# USB_to_Serial.net
KiCad netlist of a schematic drawn in Altium Designer
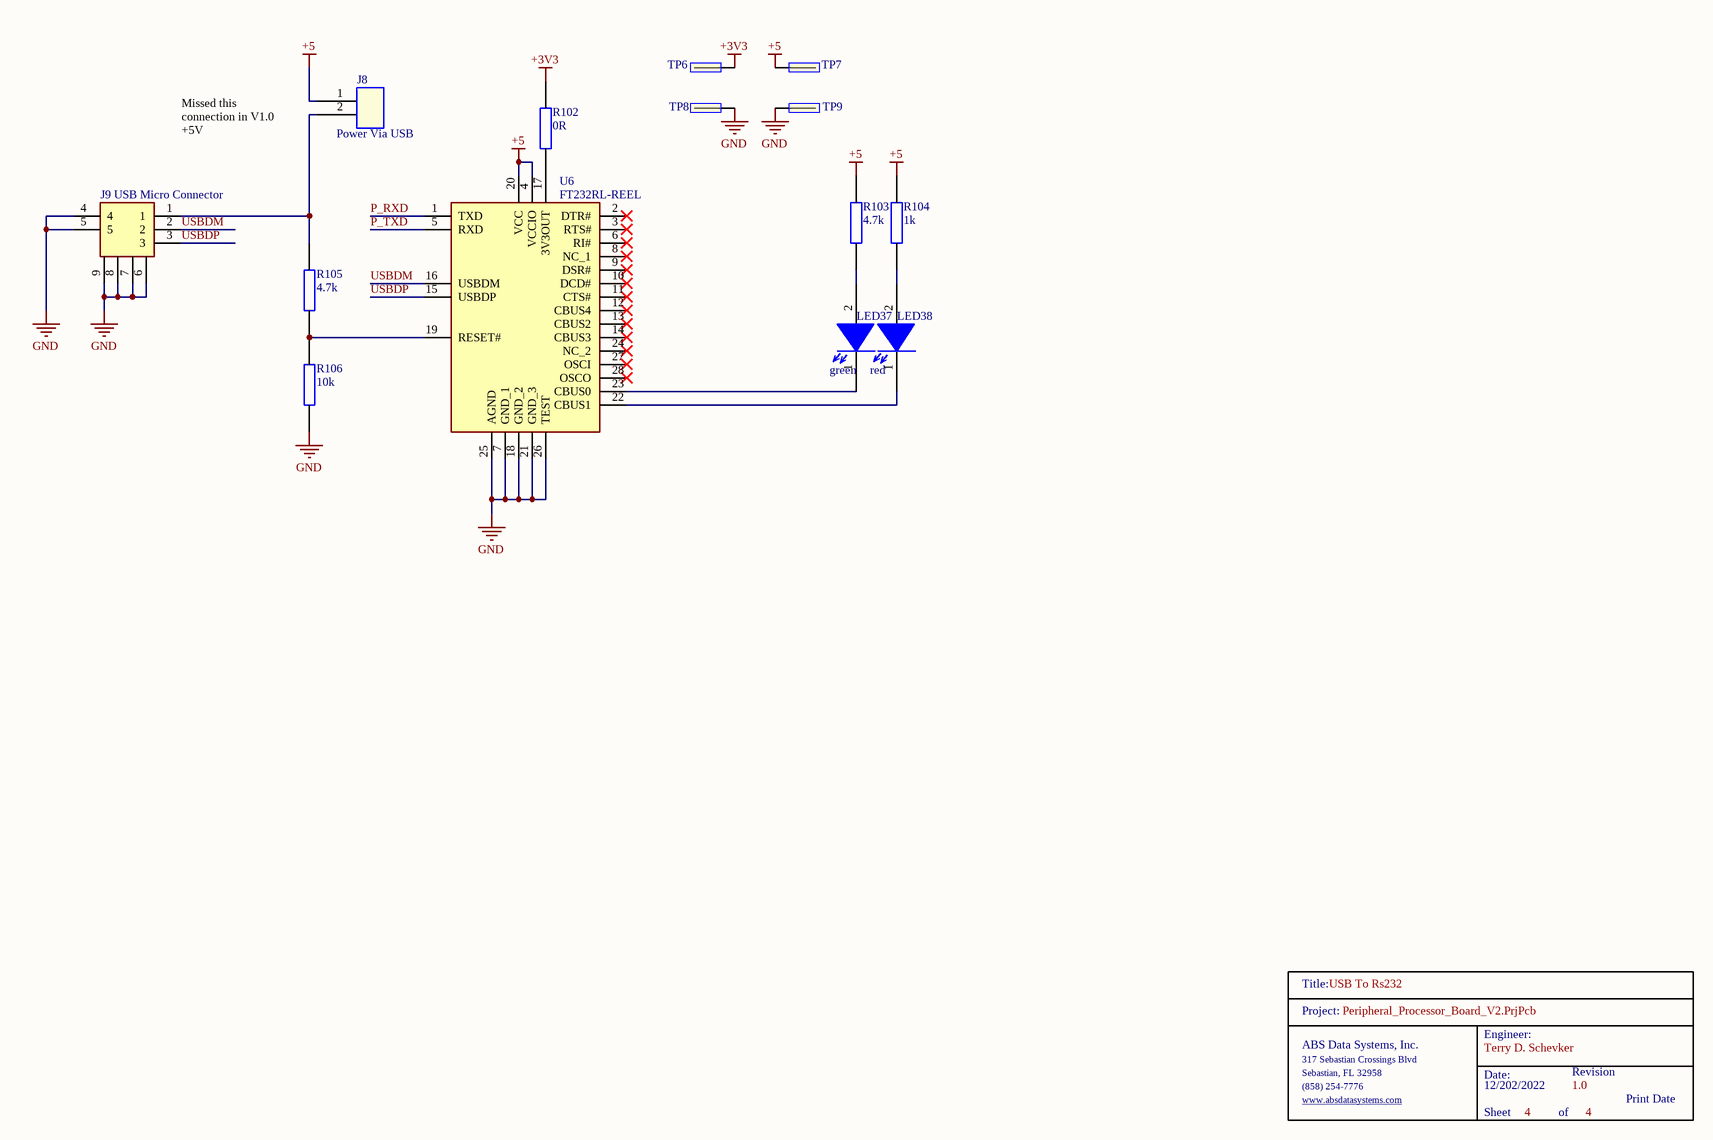
[diagram p0: USB_to_Serial.SchDoc]

(export (version "E")
  (design (tool "Eeschema 10.0.6"))
  (components
    (comp (ref "J8")
      (value "Power Via USB")
      (footprint "Jumper")
      (description "16 Pin 3x8 Through Hold Jumprts")
      (fields
        (field (name "MANUFACTURER") "Samtec")
        (field (name "MANUFACTURER PART NUMBER") "TST-108-01-G-D")
      )
      (libsource (lib "Misc") (part "Jumper"))
    )
    (comp (ref "J9")
      (value "USB Micro Connector")
      (footprint "Misc:1734035-2USB")
      (description "USB Micro Connector SMD")
      (fields
        (field (name "MOUSER2 PART NUMBER") "571-1734035-4")
        (field (name "MANUFACTURER_PART_NUMBER") "1734035-4")
      )
      (libsource (lib "Misc") (part "1734035-4"))
    )
    (comp (ref "LED37")
      (value "green")
      (footprint "0603_Diode")
      (description "Wurth Elektronik 0603 green")
      (fields
        (field (name "MANUFACTURER") "Wurth Electronics")
        (field (name "MANUFACTURER PART NUMBER") "150060GS75000")
      )
      (libsource (lib "Misc") (part "150060GS75000"))
    )
    (comp (ref "LED38")
      (value "red")
      (footprint "0603_Diode")
      (description "Wurth Elektronik 0603 red")
      (fields
        (field (name "MANUFACTURER") "Wurth Electronics")
        (field (name "MANUFACTURER PART NUMBER") "150060GS75000")
      )
      (libsource (lib "Misc") (part "150060RS75000"))
    )
    (comp (ref "R102")
      (value "0R")
      (footprint "0603")
      (description "YAGEO 0603 0 ohm")
      (fields
        (field (name "MOUSER PART NUMBER") "603-RC0603JR-070RL")
        (field (name "MANUFACTURER_PART_NUMBER") "RC0603JR-070RL")
      )
      (libsource (lib "Resistors") (part "RC0603JR-070RL"))
    )
    (comp (ref "R103")
      (value "4.7k")
      (footprint "0603")
      (description "YAGEO 0603 4.7k")
      (fields
        (field (name "MOUSER PART NUMBER") "603-RC0603JR-070RL")
        (field (name "MANUFACTURER_PART_NUMBER") "RC0603JR-070RL")
      )
      (libsource (lib "Resistors") (part "RC0603FR-104K7L"))
    )
    (comp (ref "R104")
      (value "1k")
      (footprint "0603")
      (description "YAGEO 0603 1k ohm")
      (fields
        (field (name "MOUSER PART NUMBER") "603-RC0603JR-070RL")
        (field (name "MANUFACTURER_PART_NUMBER") "RC0603JR-070RL")
      )
      (libsource (lib "Resistors") (part "AC0603FR-7W1KL_1"))
    )
    (comp (ref "R105")
      (value "4.7k")
      (footprint "0603")
      (description "YAGEO 0603 4.7k")
      (fields
        (field (name "MOUSER PART NUMBER") "603-RC0603JR-070RL")
        (field (name "MANUFACTURER_PART_NUMBER") "RC0603JR-070RL")
      )
      (libsource (lib "Resistors") (part "RC0603FR-104K7L"))
    )
    (comp (ref "R106")
      (value "10k")
      (footprint "0603")
      (description "YAGEO 0603 10k ohm")
      (fields
        (field (name "MOUSER PART NUMBER") "603-RC0603JR-070RL")
        (field (name "MANUFACTURER_PART_NUMBER") "RC0603JR-070RL")
      )
      (libsource (lib "Resistors") (part "RC0603JR-0710KL"))
    )
    (comp (ref "TitleBlock_3") (value "TitleBlock") (libsource (lib "Misc") (part "TitleBlock")))
    (comp (ref "TP6")
      (value "TP")
      (footprint "TP")
      (fields
        (field (name "MANUFACTURER") "Samtec")
        (field (name "MANUFACTURER PART NUMBER") "TST-105-01-G-D")
      )
      (libsource (lib "") (part "TP_1"))
    )
    (comp (ref "TP7")
      (value "TP")
      (footprint "TP")
      (fields
        (field (name "MANUFACTURER") "Samtec")
        (field (name "MANUFACTURER PART NUMBER") "TST-105-01-G-D")
      )
      (libsource (lib "Misc") (part "TP"))
    )
    (comp (ref "TP8")
      (value "TP")
      (footprint "TP")
      (fields
        (field (name "MANUFACTURER") "Samtec")
        (field (name "MANUFACTURER PART NUMBER") "TST-105-01-G-D")
      )
      (libsource (lib "") (part "TP_1"))
    )
    (comp (ref "TP9")
      (value "TP")
      (footprint "TP")
      (fields
        (field (name "MANUFACTURER") "Samtec")
        (field (name "MANUFACTURER PART NUMBER") "TST-105-01-G-D")
      )
      (libsource (lib "Misc") (part "TP"))
    )
    (comp (ref "U6")
      (value "FT232RL-REEL")
      (footprint "Misc:SOIC-28_Narrow")
      (description "USB-Serial SMD")
      (libsource (lib "Misc") (part "FT232RL-REEL"))
    )
  )
  (nets
    (net (code "1") (name "+3V3") (class "Default")
      (node (ref "R102") (pin "2") (pinfunction "2_2") (pintype "passive"))
      (node (ref "TP6") (pin "1") (pinfunction "1_1") (pintype "passive"))
    )
    (net (code "2") (name "+5") (class "Default")
      (node (ref "J8") (pin "1") (pinfunction "1_1") (pintype "passive"))
      (node (ref "R103") (pin "2") (pinfunction "2_2") (pintype "passive"))
      (node (ref "R104") (pin "2") (pinfunction "2_2") (pintype "passive"))
      (node (ref "TP7") (pin "1") (pinfunction "1_1") (pintype "passive"))
      (node (ref "U6") (pin "20") (pinfunction "VCC_20") (pintype "passive"))
      (node (ref "U6") (pin "4") (pinfunction "VCCIO_4") (pintype "passive"))
    )
    (net (code "3") (name "/P_RXD") (class "Default")
      (node (ref "U6") (pin "1") (pinfunction "TXD_1") (pintype "passive"))
    )
    (net (code "4") (name "/P_TXD") (class "Default")
      (node (ref "U6") (pin "5") (pinfunction "RXD_5") (pintype "passive"))
    )
    (net (code "5") (name "/USBDM") (class "Default")
      (node (ref "J9") (pin "2") (pinfunction "2_2") (pintype "passive"))
      (node (ref "U6") (pin "16") (pinfunction "USBDM_16") (pintype "passive"))
    )
    (net (code "6") (name "/USBDP") (class "Default")
      (node (ref "J9") (pin "3") (pinfunction "3_3") (pintype "passive"))
      (node (ref "U6") (pin "15") (pinfunction "USBDP_15") (pintype "passive"))
    )
    (net (code "7") (name "GND") (class "Default")
      (node (ref "J9") (pin "4") (pinfunction "4_4") (pintype "passive"))
      (node (ref "J9") (pin "5") (pinfunction "5_5") (pintype "passive"))
      (node (ref "J9") (pin "6") (pinfunction "Shield_6") (pintype "passive"))
      (node (ref "J9") (pin "7") (pinfunction "Shield_7") (pintype "passive"))
      (node (ref "J9") (pin "8") (pinfunction "Shield_8") (pintype "passive"))
      (node (ref "J9") (pin "9") (pinfunction "Shield5_9") (pintype "passive"))
      (node (ref "R106") (pin "1") (pinfunction "1_1") (pintype "passive"))
      (node (ref "TP8") (pin "1") (pinfunction "1_1") (pintype "passive"))
      (node (ref "TP9") (pin "1") (pinfunction "1_1") (pintype "passive"))
      (node (ref "U6") (pin "18") (pinfunction "GND_2_18") (pintype "passive"))
      (node (ref "U6") (pin "21") (pinfunction "GND_3_21") (pintype "passive"))
      (node (ref "U6") (pin "25") (pinfunction "AGND_25") (pintype "passive"))
      (node (ref "U6") (pin "26") (pinfunction "TEST_26") (pintype "passive"))
      (node (ref "U6") (pin "7") (pinfunction "GND_1_7") (pintype "passive"))
    )
    (net (code "8") (name "Net-(J8-Pad2)") (class "Default")
      (node (ref "J8") (pin "2") (pinfunction "2_2") (pintype "passive"))
      (node (ref "J9") (pin "1") (pinfunction "1_1") (pintype "passive"))
      (node (ref "R105") (pin "2") (pinfunction "2_2") (pintype "passive"))
    )
    (net (code "9") (name "Net-(LED37-A)") (class "Default")
      (node (ref "LED37") (pin "2") (pinfunction "A_2") (pintype "passive"))
      (node (ref "R103") (pin "1") (pinfunction "1_1") (pintype "passive"))
    )
    (net (code "10") (name "Net-(LED37-K)") (class "Default")
      (node (ref "LED37") (pin "1") (pinfunction "K_1") (pintype "passive"))
      (node (ref "U6") (pin "23") (pinfunction "CBUS0_23") (pintype "passive"))
    )
    (net (code "11") (name "Net-(LED38-A)") (class "Default")
      (node (ref "LED38") (pin "2") (pinfunction "A_2") (pintype "passive"))
      (node (ref "R104") (pin "1") (pinfunction "1_1") (pintype "passive"))
    )
    (net (code "12") (name "Net-(LED38-K)") (class "Default")
      (node (ref "LED38") (pin "1") (pinfunction "K_1") (pintype "passive"))
      (node (ref "U6") (pin "22") (pinfunction "CBUS1_22") (pintype "passive"))
    )
    (net (code "13") (name "Net-(U6-3V3OUT)") (class "Default")
      (node (ref "R102") (pin "1") (pinfunction "1_1") (pintype "passive"))
      (node (ref "U6") (pin "17") (pinfunction "3V3OUT_17") (pintype "passive"))
    )
    (net (code "14") (name "Net-(U6-RESET#)") (class "Default")
      (node (ref "R105") (pin "1") (pinfunction "1_1") (pintype "passive"))
      (node (ref "R106") (pin "2") (pinfunction "2_2") (pintype "passive"))
      (node (ref "U6") (pin "19") (pinfunction "RESET#_19") (pintype "passive"))
    )
    (net (code "15") (name "unconnected-(U6-CBUS2-Pad13)") (class "Default")
      (node (ref "U6") (pin "13") (pinfunction "CBUS2_13") (pintype "passive+no_connect"))
    )
    (net (code "16") (name "unconnected-(U6-CBUS3-Pad14)") (class "Default")
      (node (ref "U6") (pin "14") (pinfunction "CBUS3_14") (pintype "passive+no_connect"))
    )
    (net (code "17") (name "unconnected-(U6-CBUS4-Pad12)") (class "Default")
      (node (ref "U6") (pin "12") (pinfunction "CBUS4_12") (pintype "passive+no_connect"))
    )
    (net (code "18") (name "unconnected-(U6-CTS#-Pad11)") (class "Default")
      (node (ref "U6") (pin "11") (pinfunction "CTS#_11") (pintype "passive+no_connect"))
    )
    (net (code "19") (name "unconnected-(U6-DCD#-Pad10)") (class "Default")
      (node (ref "U6") (pin "10") (pinfunction "DCD#_10") (pintype "passive+no_connect"))
    )
    (net (code "20") (name "unconnected-(U6-DSR#-Pad9)") (class "Default")
      (node (ref "U6") (pin "9") (pinfunction "DSR#_9") (pintype "passive+no_connect"))
    )
    (net (code "21") (name "unconnected-(U6-DTR#-Pad2)") (class "Default")
      (node (ref "U6") (pin "2") (pinfunction "DTR#_2") (pintype "passive+no_connect"))
    )
    (net (code "22") (name "unconnected-(U6-NC_1-Pad8)") (class "Default")
      (node (ref "U6") (pin "8") (pinfunction "NC_1_8") (pintype "passive+no_connect"))
    )
    (net (code "23") (name "unconnected-(U6-NC_2-Pad24)") (class "Default")
      (node (ref "U6") (pin "24") (pinfunction "NC_2_24") (pintype "passive+no_connect"))
    )
    (net (code "24") (name "unconnected-(U6-OSCI-Pad27)") (class "Default")
      (node (ref "U6") (pin "27") (pinfunction "OSCI_27") (pintype "passive+no_connect"))
    )
    (net (code "25") (name "unconnected-(U6-OSCO-Pad28)") (class "Default")
      (node (ref "U6") (pin "28") (pinfunction "OSCO_28") (pintype "passive+no_connect"))
    )
    (net (code "26") (name "unconnected-(U6-RI#-Pad6)") (class "Default")
      (node (ref "U6") (pin "6") (pinfunction "RI#_6") (pintype "passive+no_connect"))
    )
    (net (code "27") (name "unconnected-(U6-RTS#-Pad3)") (class "Default")
      (node (ref "U6") (pin "3") (pinfunction "RTS#_3") (pintype "passive+no_connect"))
    )
  )
)
